# LED_controller.net
KiCad netlist of a schematic drawn in EAGLE
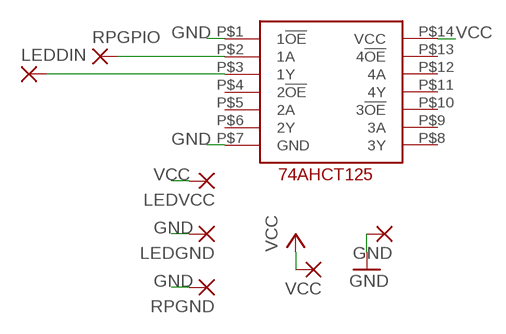
[diagram p0: schematic, sheet 1]

(export (version "E")
  (design (tool "Eeschema 10.0.6"))
  (components
    (comp (ref "GND")
      (value "1,6/0,9")
      (footprint "eagle-import:1,6_0,9")
      (libsource (lib "eagle-import") (part "1,6/0,9"))
    )
    (comp (ref "LEDDIN")
      (value "1,6/0,9")
      (footprint "eagle-import:1,6_0,9")
      (libsource (lib "eagle-import") (part "1,6/0,9"))
    )
    (comp (ref "LEDGND")
      (value "1,6/0,9")
      (footprint "eagle-import:1,6_0,9")
      (libsource (lib "eagle-import") (part "1,6/0,9"))
    )
    (comp (ref "LEDVCC")
      (value "1,6/0,9")
      (footprint "eagle-import:1,6_0,9")
      (libsource (lib "eagle-import") (part "1,6/0,9"))
    )
    (comp (ref "RPGND")
      (value "1,6/0,9")
      (footprint "eagle-import:1,6_0,9")
      (libsource (lib "eagle-import") (part "1,6/0,9"))
    )
    (comp (ref "RPGPIO")
      (value "1,6/0,9")
      (footprint "eagle-import:1,6_0,9")
      (libsource (lib "eagle-import") (part "1,6/0,9"))
    )
    (comp (ref "U$1")
      (value "74AHCT125N14")
      (footprint "eagle-import:N14")
      (libsource (lib "eagle-import") (part "74AHCT125N14"))
    )
    (comp (ref "VCC")
      (value "1,6/0,9")
      (footprint "eagle-import:1,6_0,9")
      (libsource (lib "eagle-import") (part "1,6/0,9"))
    )
  )
  (nets
    (net (code "1") (name "GND") (class "Default")
      (node (ref "GND") (pin "1") (pinfunction "P_1") (pintype "passive"))
      (node (ref "LEDGND") (pin "1") (pinfunction "P_1") (pintype "passive"))
      (node (ref "RPGND") (pin "1") (pinfunction "P_1") (pintype "passive"))
      (node (ref "U$1") (pin "P$1") (pinfunction "1~{OE}_P$1") (pintype "bidirectional"))
      (node (ref "U$1") (pin "P$7") (pinfunction "GND_P$7") (pintype "bidirectional"))
    )
    (net (code "2") (name "Net-(LEDDIN-P)") (class "Default")
      (node (ref "LEDDIN") (pin "1") (pinfunction "P_1") (pintype "passive"))
      (node (ref "U$1") (pin "P$3") (pinfunction "1Y_P$3") (pintype "bidirectional"))
    )
    (net (code "3") (name "Net-(RPGPIO-P)") (class "Default")
      (node (ref "RPGPIO") (pin "1") (pinfunction "P_1") (pintype "passive"))
      (node (ref "U$1") (pin "P$2") (pinfunction "1A_P$2") (pintype "bidirectional"))
    )
    (net (code "4") (name "VCC") (class "Default")
      (node (ref "LEDVCC") (pin "1") (pinfunction "P_1") (pintype "passive"))
      (node (ref "U$1") (pin "P$14") (pinfunction "VCC_P$14") (pintype "bidirectional"))
      (node (ref "VCC") (pin "1") (pinfunction "P_1") (pintype "passive"))
    )
    (net (code "5") (name "unconnected-(U$1-2A-PadP$5)") (class "Default")
      (node (ref "U$1") (pin "P$5") (pinfunction "2A_P$5") (pintype "bidirectional"))
    )
    (net (code "6") (name "unconnected-(U$1-2Y-PadP$6)") (class "Default")
      (node (ref "U$1") (pin "P$6") (pinfunction "2Y_P$6") (pintype "bidirectional"))
    )
    (net (code "7") (name "unconnected-(U$1-2~{OE}-PadP$4)") (class "Default")
      (node (ref "U$1") (pin "P$4") (pinfunction "2~{OE}_P$4") (pintype "bidirectional"))
    )
    (net (code "8") (name "unconnected-(U$1-3A-PadP$9)") (class "Default")
      (node (ref "U$1") (pin "P$9") (pinfunction "3A_P$9") (pintype "bidirectional"))
    )
    (net (code "9") (name "unconnected-(U$1-3Y-PadP$8)") (class "Default")
      (node (ref "U$1") (pin "P$8") (pinfunction "3Y_P$8") (pintype "bidirectional"))
    )
    (net (code "10") (name "unconnected-(U$1-3~{OE}-PadP$10)") (class "Default")
      (node (ref "U$1") (pin "P$10") (pinfunction "3~{OE}_P$10") (pintype "bidirectional"))
    )
    (net (code "11") (name "unconnected-(U$1-4A-PadP$12)") (class "Default")
      (node (ref "U$1") (pin "P$12") (pinfunction "4A_P$12") (pintype "bidirectional"))
    )
    (net (code "12") (name "unconnected-(U$1-4Y-PadP$11)") (class "Default")
      (node (ref "U$1") (pin "P$11") (pinfunction "4Y_P$11") (pintype "bidirectional"))
    )
    (net (code "13") (name "unconnected-(U$1-4~{OE}-PadP$13)") (class "Default")
      (node (ref "U$1") (pin "P$13") (pinfunction "4~{OE}_P$13") (pintype "bidirectional"))
    )
  )
)
